# D_Input.net
KiCad netlist of a schematic drawn in Altium Designer
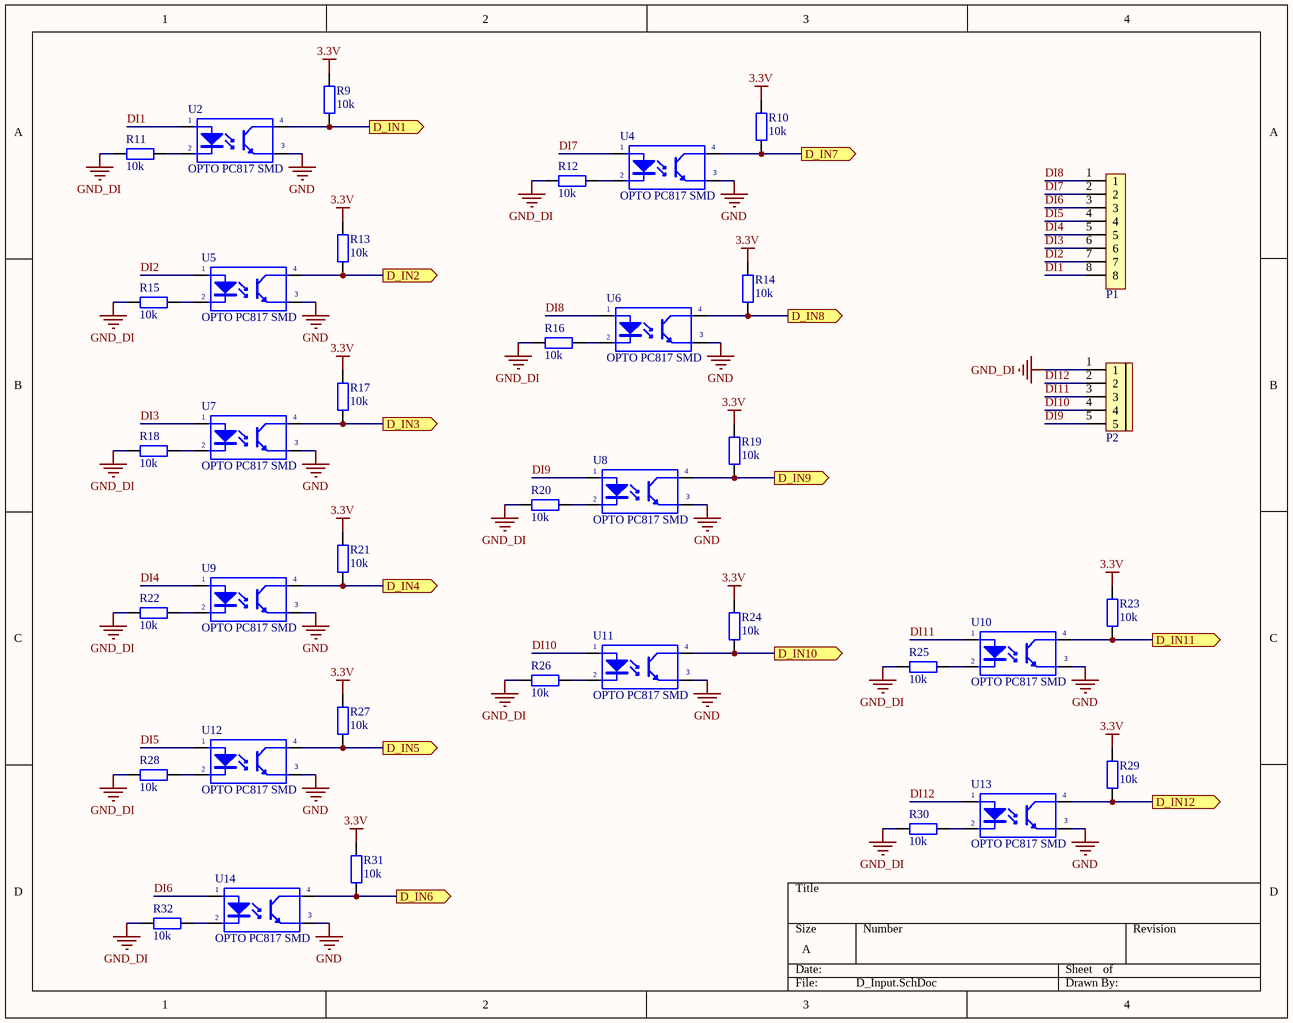
[diagram p0: D_Input.SchDoc]

(export (version "E")
  (design (tool "Eeschema 10.0.6"))
  (components
    (comp (ref "P1")
      (value "CON 8 EDG5.08")
      (footprint "CON 8 8EDG5.08")
      (description "Cắm")
      (libsource (lib "Altium_Lib_by_KhueNguyenCreator") (part "CON 8 EDG5.08"))
    )
    (comp (ref "P2")
      (value "CON 5 EDG5.08")
      (footprint "CON 5 5EDG5.08")
      (description "Cắm")
      (libsource (lib "Altium_Lib_by_KhueNguyenCreator") (part "CON 5 EDG5.08"))
    )
    (comp (ref "R9")
      (value "10k")
      (footprint "tro smd 0805")
      (description "Dán")
      (libsource (lib "Altium_Lib_by_KhueNguyenCreator") (part "Tro 0805 1% 10k"))
    )
    (comp (ref "R10")
      (value "10k")
      (footprint "tro smd 0805")
      (description "Dán")
      (libsource (lib "Altium_Lib_by_KhueNguyenCreator") (part "Tro 0805 1% 10k"))
    )
    (comp (ref "R11")
      (value "10k")
      (footprint "tro smd 0805")
      (description "Dán")
      (libsource (lib "Altium_Lib_by_KhueNguyenCreator") (part "Tro 0805 1% 10k"))
    )
    (comp (ref "R12")
      (value "10k")
      (footprint "tro smd 0805")
      (description "Dán")
      (libsource (lib "Altium_Lib_by_KhueNguyenCreator") (part "Tro 0805 1% 10k"))
    )
    (comp (ref "R13")
      (value "10k")
      (footprint "tro smd 0805")
      (description "Dán")
      (libsource (lib "Altium_Lib_by_KhueNguyenCreator") (part "Tro 0805 1% 10k"))
    )
    (comp (ref "R14")
      (value "10k")
      (footprint "tro smd 0805")
      (description "Dán")
      (libsource (lib "Altium_Lib_by_KhueNguyenCreator") (part "Tro 0805 1% 10k"))
    )
    (comp (ref "R15")
      (value "10k")
      (footprint "tro smd 0805")
      (description "Dán")
      (libsource (lib "Altium_Lib_by_KhueNguyenCreator") (part "Tro 0805 1% 10k"))
    )
    (comp (ref "R16")
      (value "10k")
      (footprint "tro smd 0805")
      (description "Dán")
      (libsource (lib "Altium_Lib_by_KhueNguyenCreator") (part "Tro 0805 1% 10k"))
    )
    (comp (ref "R17")
      (value "10k")
      (footprint "tro smd 0805")
      (description "Dán")
      (libsource (lib "Altium_Lib_by_KhueNguyenCreator") (part "Tro 0805 1% 10k"))
    )
    (comp (ref "R18")
      (value "10k")
      (footprint "tro smd 0805")
      (description "Dán")
      (libsource (lib "Altium_Lib_by_KhueNguyenCreator") (part "Tro 0805 1% 10k"))
    )
    (comp (ref "R19")
      (value "10k")
      (footprint "tro smd 0805")
      (description "Dán")
      (libsource (lib "Altium_Lib_by_KhueNguyenCreator") (part "Tro 0805 1% 10k"))
    )
    (comp (ref "R20")
      (value "10k")
      (footprint "tro smd 0805")
      (description "Dán")
      (libsource (lib "Altium_Lib_by_KhueNguyenCreator") (part "Tro 0805 1% 10k"))
    )
    (comp (ref "R21")
      (value "10k")
      (footprint "tro smd 0805")
      (description "Dán")
      (libsource (lib "Altium_Lib_by_KhueNguyenCreator") (part "Tro 0805 1% 10k"))
    )
    (comp (ref "R22")
      (value "10k")
      (footprint "tro smd 0805")
      (description "Dán")
      (libsource (lib "Altium_Lib_by_KhueNguyenCreator") (part "Tro 0805 1% 10k"))
    )
    (comp (ref "R23")
      (value "10k")
      (footprint "tro smd 0805")
      (description "Dán")
      (libsource (lib "Altium_Lib_by_KhueNguyenCreator") (part "Tro 0805 1% 10k"))
    )
    (comp (ref "R24")
      (value "10k")
      (footprint "tro smd 0805")
      (description "Dán")
      (libsource (lib "Altium_Lib_by_KhueNguyenCreator") (part "Tro 0805 1% 10k"))
    )
    (comp (ref "R25")
      (value "10k")
      (footprint "tro smd 0805")
      (description "Dán")
      (libsource (lib "Altium_Lib_by_KhueNguyenCreator") (part "Tro 0805 1% 10k"))
    )
    (comp (ref "R26")
      (value "10k")
      (footprint "tro smd 0805")
      (description "Dán")
      (libsource (lib "Altium_Lib_by_KhueNguyenCreator") (part "Tro 0805 1% 10k"))
    )
    (comp (ref "R27")
      (value "10k")
      (footprint "tro smd 0805")
      (description "Dán")
      (libsource (lib "Altium_Lib_by_KhueNguyenCreator") (part "Tro 0805 1% 10k"))
    )
    (comp (ref "R28")
      (value "10k")
      (footprint "tro smd 0805")
      (description "Dán")
      (libsource (lib "Altium_Lib_by_KhueNguyenCreator") (part "Tro 0805 1% 10k"))
    )
    (comp (ref "R29")
      (value "10k")
      (footprint "tro smd 0805")
      (description "Dán")
      (libsource (lib "Altium_Lib_by_KhueNguyenCreator") (part "Tro 0805 1% 10k"))
    )
    (comp (ref "R30")
      (value "10k")
      (footprint "tro smd 0805")
      (description "Dán")
      (libsource (lib "Altium_Lib_by_KhueNguyenCreator") (part "Tro 0805 1% 10k"))
    )
    (comp (ref "R31")
      (value "10k")
      (footprint "tro smd 0805")
      (description "Dán")
      (libsource (lib "Altium_Lib_by_KhueNguyenCreator") (part "Tro 0805 1% 10k"))
    )
    (comp (ref "R32")
      (value "10k")
      (footprint "tro smd 0805")
      (description "Dán")
      (libsource (lib "Altium_Lib_by_KhueNguyenCreator") (part "Tro 0805 1% 10k"))
    )
    (comp (ref "U2")
      (value "OPTO PC817 SMD")
      (footprint "SOP4")
      (description "Single Opto")
      (libsource (lib "Altium_Lib_by_KhueNguyenCreator") (part "OPTO PC817 SMD"))
    )
    (comp (ref "U4")
      (value "OPTO PC817 SMD")
      (footprint "SOP4")
      (description "Single Opto")
      (libsource (lib "Altium_Lib_by_KhueNguyenCreator") (part "OPTO PC817 SMD"))
    )
    (comp (ref "U5")
      (value "OPTO PC817 SMD")
      (footprint "SOP4")
      (description "Single Opto")
      (libsource (lib "Altium_Lib_by_KhueNguyenCreator") (part "OPTO PC817 SMD"))
    )
    (comp (ref "U6")
      (value "OPTO PC817 SMD")
      (footprint "SOP4")
      (description "Single Opto")
      (libsource (lib "Altium_Lib_by_KhueNguyenCreator") (part "OPTO PC817 SMD"))
    )
    (comp (ref "U7")
      (value "OPTO PC817 SMD")
      (footprint "SOP4")
      (description "Single Opto")
      (libsource (lib "Altium_Lib_by_KhueNguyenCreator") (part "OPTO PC817 SMD"))
    )
    (comp (ref "U8")
      (value "OPTO PC817 SMD")
      (footprint "SOP4")
      (description "Single Opto")
      (libsource (lib "Altium_Lib_by_KhueNguyenCreator") (part "OPTO PC817 SMD"))
    )
    (comp (ref "U9")
      (value "OPTO PC817 SMD")
      (footprint "SOP4")
      (description "Single Opto")
      (libsource (lib "Altium_Lib_by_KhueNguyenCreator") (part "OPTO PC817 SMD"))
    )
    (comp (ref "U10")
      (value "OPTO PC817 SMD")
      (footprint "SOP4")
      (description "Single Opto")
      (libsource (lib "Altium_Lib_by_KhueNguyenCreator") (part "OPTO PC817 SMD"))
    )
    (comp (ref "U11")
      (value "OPTO PC817 SMD")
      (footprint "SOP4")
      (description "Single Opto")
      (libsource (lib "Altium_Lib_by_KhueNguyenCreator") (part "OPTO PC817 SMD"))
    )
    (comp (ref "U12")
      (value "OPTO PC817 SMD")
      (footprint "SOP4")
      (description "Single Opto")
      (libsource (lib "Altium_Lib_by_KhueNguyenCreator") (part "OPTO PC817 SMD"))
    )
    (comp (ref "U13")
      (value "OPTO PC817 SMD")
      (footprint "SOP4")
      (description "Single Opto")
      (libsource (lib "Altium_Lib_by_KhueNguyenCreator") (part "OPTO PC817 SMD"))
    )
    (comp (ref "U14")
      (value "OPTO PC817 SMD")
      (footprint "SOP4")
      (description "Single Opto")
      (libsource (lib "Altium_Lib_by_KhueNguyenCreator") (part "OPTO PC817 SMD"))
    )
  )
  (nets
    (net (code "1") (name "/DI1") (class "Default")
      (node (ref "P1") (pin "8") (pinfunction "8_8") (pintype "passive"))
      (node (ref "U2") (pin "1") (pinfunction "A_1") (pintype "passive"))
    )
    (net (code "2") (name "/DI2") (class "Default")
      (node (ref "P1") (pin "7") (pinfunction "7_7") (pintype "passive"))
      (node (ref "U5") (pin "1") (pinfunction "A_1") (pintype "passive"))
    )
    (net (code "3") (name "/DI3") (class "Default")
      (node (ref "P1") (pin "6") (pinfunction "6_6") (pintype "passive"))
      (node (ref "U7") (pin "1") (pinfunction "A_1") (pintype "passive"))
    )
    (net (code "4") (name "/DI4") (class "Default")
      (node (ref "P1") (pin "5") (pinfunction "5_5") (pintype "passive"))
      (node (ref "U9") (pin "1") (pinfunction "A_1") (pintype "passive"))
    )
    (net (code "5") (name "/DI5") (class "Default")
      (node (ref "P1") (pin "4") (pinfunction "4_4") (pintype "passive"))
      (node (ref "U12") (pin "1") (pinfunction "A_1") (pintype "passive"))
    )
    (net (code "6") (name "/DI6") (class "Default")
      (node (ref "P1") (pin "3") (pinfunction "3_3") (pintype "passive"))
      (node (ref "U14") (pin "1") (pinfunction "A_1") (pintype "passive"))
    )
    (net (code "7") (name "/DI7") (class "Default")
      (node (ref "P1") (pin "2") (pinfunction "2_2") (pintype "passive"))
      (node (ref "U4") (pin "1") (pinfunction "A_1") (pintype "passive"))
    )
    (net (code "8") (name "/DI8") (class "Default")
      (node (ref "P1") (pin "1") (pinfunction "1_1") (pintype "passive"))
      (node (ref "U6") (pin "1") (pinfunction "A_1") (pintype "passive"))
    )
    (net (code "9") (name "/DI9") (class "Default")
      (node (ref "P2") (pin "5") (pinfunction "5_5") (pintype "passive"))
      (node (ref "U8") (pin "1") (pinfunction "A_1") (pintype "passive"))
    )
    (net (code "10") (name "/DI10") (class "Default")
      (node (ref "P2") (pin "4") (pinfunction "4_4") (pintype "passive"))
      (node (ref "U11") (pin "1") (pinfunction "A_1") (pintype "passive"))
    )
    (net (code "11") (name "/DI11") (class "Default")
      (node (ref "P2") (pin "3") (pinfunction "3_3") (pintype "passive"))
      (node (ref "U10") (pin "1") (pinfunction "A_1") (pintype "passive"))
    )
    (net (code "12") (name "/DI12") (class "Default")
      (node (ref "P2") (pin "2") (pinfunction "2_2") (pintype "passive"))
      (node (ref "U13") (pin "1") (pinfunction "A_1") (pintype "passive"))
    )
    (net (code "13") (name "/D_IN1") (class "Default")
      (node (ref "R9") (pin "1") (pinfunction "1_1") (pintype "passive"))
      (node (ref "U2") (pin "4") (pinfunction "C_4") (pintype "passive"))
    )
    (net (code "14") (name "/D_IN2") (class "Default")
      (node (ref "R13") (pin "1") (pinfunction "1_1") (pintype "passive"))
      (node (ref "U5") (pin "4") (pinfunction "C_4") (pintype "passive"))
    )
    (net (code "15") (name "/D_IN3") (class "Default")
      (node (ref "R17") (pin "1") (pinfunction "1_1") (pintype "passive"))
      (node (ref "U7") (pin "4") (pinfunction "C_4") (pintype "passive"))
    )
    (net (code "16") (name "/D_IN4") (class "Default")
      (node (ref "R21") (pin "1") (pinfunction "1_1") (pintype "passive"))
      (node (ref "U9") (pin "4") (pinfunction "C_4") (pintype "passive"))
    )
    (net (code "17") (name "/D_IN5") (class "Default")
      (node (ref "R27") (pin "1") (pinfunction "1_1") (pintype "passive"))
      (node (ref "U12") (pin "4") (pinfunction "C_4") (pintype "passive"))
    )
    (net (code "18") (name "/D_IN6") (class "Default")
      (node (ref "R31") (pin "1") (pinfunction "1_1") (pintype "passive"))
      (node (ref "U14") (pin "4") (pinfunction "C_4") (pintype "passive"))
    )
    (net (code "19") (name "/D_IN7") (class "Default")
      (node (ref "R10") (pin "1") (pinfunction "1_1") (pintype "passive"))
      (node (ref "U4") (pin "4") (pinfunction "C_4") (pintype "passive"))
    )
    (net (code "20") (name "/D_IN8") (class "Default")
      (node (ref "R14") (pin "1") (pinfunction "1_1") (pintype "passive"))
      (node (ref "U6") (pin "4") (pinfunction "C_4") (pintype "passive"))
    )
    (net (code "21") (name "/D_IN9") (class "Default")
      (node (ref "R19") (pin "1") (pinfunction "1_1") (pintype "passive"))
      (node (ref "U8") (pin "4") (pinfunction "C_4") (pintype "passive"))
    )
    (net (code "22") (name "/D_IN10") (class "Default")
      (node (ref "R24") (pin "1") (pinfunction "1_1") (pintype "passive"))
      (node (ref "U11") (pin "4") (pinfunction "C_4") (pintype "passive"))
    )
    (net (code "23") (name "/D_IN11") (class "Default")
      (node (ref "R23") (pin "1") (pinfunction "1_1") (pintype "passive"))
      (node (ref "U10") (pin "4") (pinfunction "C_4") (pintype "passive"))
    )
    (net (code "24") (name "/D_IN12") (class "Default")
      (node (ref "R29") (pin "1") (pinfunction "1_1") (pintype "passive"))
      (node (ref "U13") (pin "4") (pinfunction "C_4") (pintype "passive"))
    )
    (net (code "25") (name "3.3V") (class "Default")
      (node (ref "R10") (pin "2") (pinfunction "2_2") (pintype "passive"))
      (node (ref "R13") (pin "2") (pinfunction "2_2") (pintype "passive"))
      (node (ref "R14") (pin "2") (pinfunction "2_2") (pintype "passive"))
      (node (ref "R17") (pin "2") (pinfunction "2_2") (pintype "passive"))
      (node (ref "R19") (pin "2") (pinfunction "2_2") (pintype "passive"))
      (node (ref "R21") (pin "2") (pinfunction "2_2") (pintype "passive"))
      (node (ref "R23") (pin "2") (pinfunction "2_2") (pintype "passive"))
      (node (ref "R24") (pin "2") (pinfunction "2_2") (pintype "passive"))
      (node (ref "R27") (pin "2") (pinfunction "2_2") (pintype "passive"))
      (node (ref "R29") (pin "2") (pinfunction "2_2") (pintype "passive"))
      (node (ref "R31") (pin "2") (pinfunction "2_2") (pintype "passive"))
      (node (ref "R9") (pin "2") (pinfunction "2_2") (pintype "passive"))
    )
    (net (code "26") (name "GND") (class "Default")
      (node (ref "U10") (pin "3") (pinfunction "E_3") (pintype "passive"))
      (node (ref "U11") (pin "3") (pinfunction "E_3") (pintype "passive"))
      (node (ref "U12") (pin "3") (pinfunction "E_3") (pintype "passive"))
      (node (ref "U13") (pin "3") (pinfunction "E_3") (pintype "passive"))
      (node (ref "U14") (pin "3") (pinfunction "E_3") (pintype "passive"))
      (node (ref "U2") (pin "3") (pinfunction "E_3") (pintype "passive"))
      (node (ref "U4") (pin "3") (pinfunction "E_3") (pintype "passive"))
      (node (ref "U5") (pin "3") (pinfunction "E_3") (pintype "passive"))
      (node (ref "U6") (pin "3") (pinfunction "E_3") (pintype "passive"))
      (node (ref "U7") (pin "3") (pinfunction "E_3") (pintype "passive"))
      (node (ref "U8") (pin "3") (pinfunction "E_3") (pintype "passive"))
      (node (ref "U9") (pin "3") (pinfunction "E_3") (pintype "passive"))
    )
    (net (code "27") (name "GND_DI") (class "Default")
      (node (ref "P2") (pin "1") (pinfunction "1_1") (pintype "passive"))
      (node (ref "R11") (pin "1") (pinfunction "1_1") (pintype "passive"))
      (node (ref "R12") (pin "1") (pinfunction "1_1") (pintype "passive"))
      (node (ref "R15") (pin "1") (pinfunction "1_1") (pintype "passive"))
      (node (ref "R16") (pin "1") (pinfunction "1_1") (pintype "passive"))
      (node (ref "R18") (pin "1") (pinfunction "1_1") (pintype "passive"))
      (node (ref "R20") (pin "1") (pinfunction "1_1") (pintype "passive"))
      (node (ref "R22") (pin "1") (pinfunction "1_1") (pintype "passive"))
      (node (ref "R25") (pin "1") (pinfunction "1_1") (pintype "passive"))
      (node (ref "R26") (pin "1") (pinfunction "1_1") (pintype "passive"))
      (node (ref "R28") (pin "1") (pinfunction "1_1") (pintype "passive"))
      (node (ref "R30") (pin "1") (pinfunction "1_1") (pintype "passive"))
      (node (ref "R32") (pin "1") (pinfunction "1_1") (pintype "passive"))
    )
    (net (code "28") (name "Net-(U2-K)") (class "Default")
      (node (ref "R11") (pin "2") (pinfunction "2_2") (pintype "passive"))
      (node (ref "U2") (pin "2") (pinfunction "K_2") (pintype "passive"))
    )
    (net (code "29") (name "Net-(U4-K)") (class "Default")
      (node (ref "R12") (pin "2") (pinfunction "2_2") (pintype "passive"))
      (node (ref "U4") (pin "2") (pinfunction "K_2") (pintype "passive"))
    )
    (net (code "30") (name "Net-(U5-K)") (class "Default")
      (node (ref "R15") (pin "2") (pinfunction "2_2") (pintype "passive"))
      (node (ref "U5") (pin "2") (pinfunction "K_2") (pintype "passive"))
    )
    (net (code "31") (name "Net-(U6-K)") (class "Default")
      (node (ref "R16") (pin "2") (pinfunction "2_2") (pintype "passive"))
      (node (ref "U6") (pin "2") (pinfunction "K_2") (pintype "passive"))
    )
    (net (code "32") (name "Net-(U7-K)") (class "Default")
      (node (ref "R18") (pin "2") (pinfunction "2_2") (pintype "passive"))
      (node (ref "U7") (pin "2") (pinfunction "K_2") (pintype "passive"))
    )
    (net (code "33") (name "Net-(U8-K)") (class "Default")
      (node (ref "R20") (pin "2") (pinfunction "2_2") (pintype "passive"))
      (node (ref "U8") (pin "2") (pinfunction "K_2") (pintype "passive"))
    )
    (net (code "34") (name "Net-(U9-K)") (class "Default")
      (node (ref "R22") (pin "2") (pinfunction "2_2") (pintype "passive"))
      (node (ref "U9") (pin "2") (pinfunction "K_2") (pintype "passive"))
    )
    (net (code "35") (name "Net-(U10-K)") (class "Default")
      (node (ref "R25") (pin "2") (pinfunction "2_2") (pintype "passive"))
      (node (ref "U10") (pin "2") (pinfunction "K_2") (pintype "passive"))
    )
    (net (code "36") (name "Net-(U11-K)") (class "Default")
      (node (ref "R26") (pin "2") (pinfunction "2_2") (pintype "passive"))
      (node (ref "U11") (pin "2") (pinfunction "K_2") (pintype "passive"))
    )
    (net (code "37") (name "Net-(U12-K)") (class "Default")
      (node (ref "R28") (pin "2") (pinfunction "2_2") (pintype "passive"))
      (node (ref "U12") (pin "2") (pinfunction "K_2") (pintype "passive"))
    )
    (net (code "38") (name "Net-(U13-K)") (class "Default")
      (node (ref "R30") (pin "2") (pinfunction "2_2") (pintype "passive"))
      (node (ref "U13") (pin "2") (pinfunction "K_2") (pintype "passive"))
    )
    (net (code "39") (name "Net-(U14-K)") (class "Default")
      (node (ref "R32") (pin "2") (pinfunction "2_2") (pintype "passive"))
      (node (ref "U14") (pin "2") (pinfunction "K_2") (pintype "passive"))
    )
  )
)
